# ATMega328-AD_DA_IO-V51-Eagle-Full.net
KiCad netlist of a schematic drawn in EAGLE
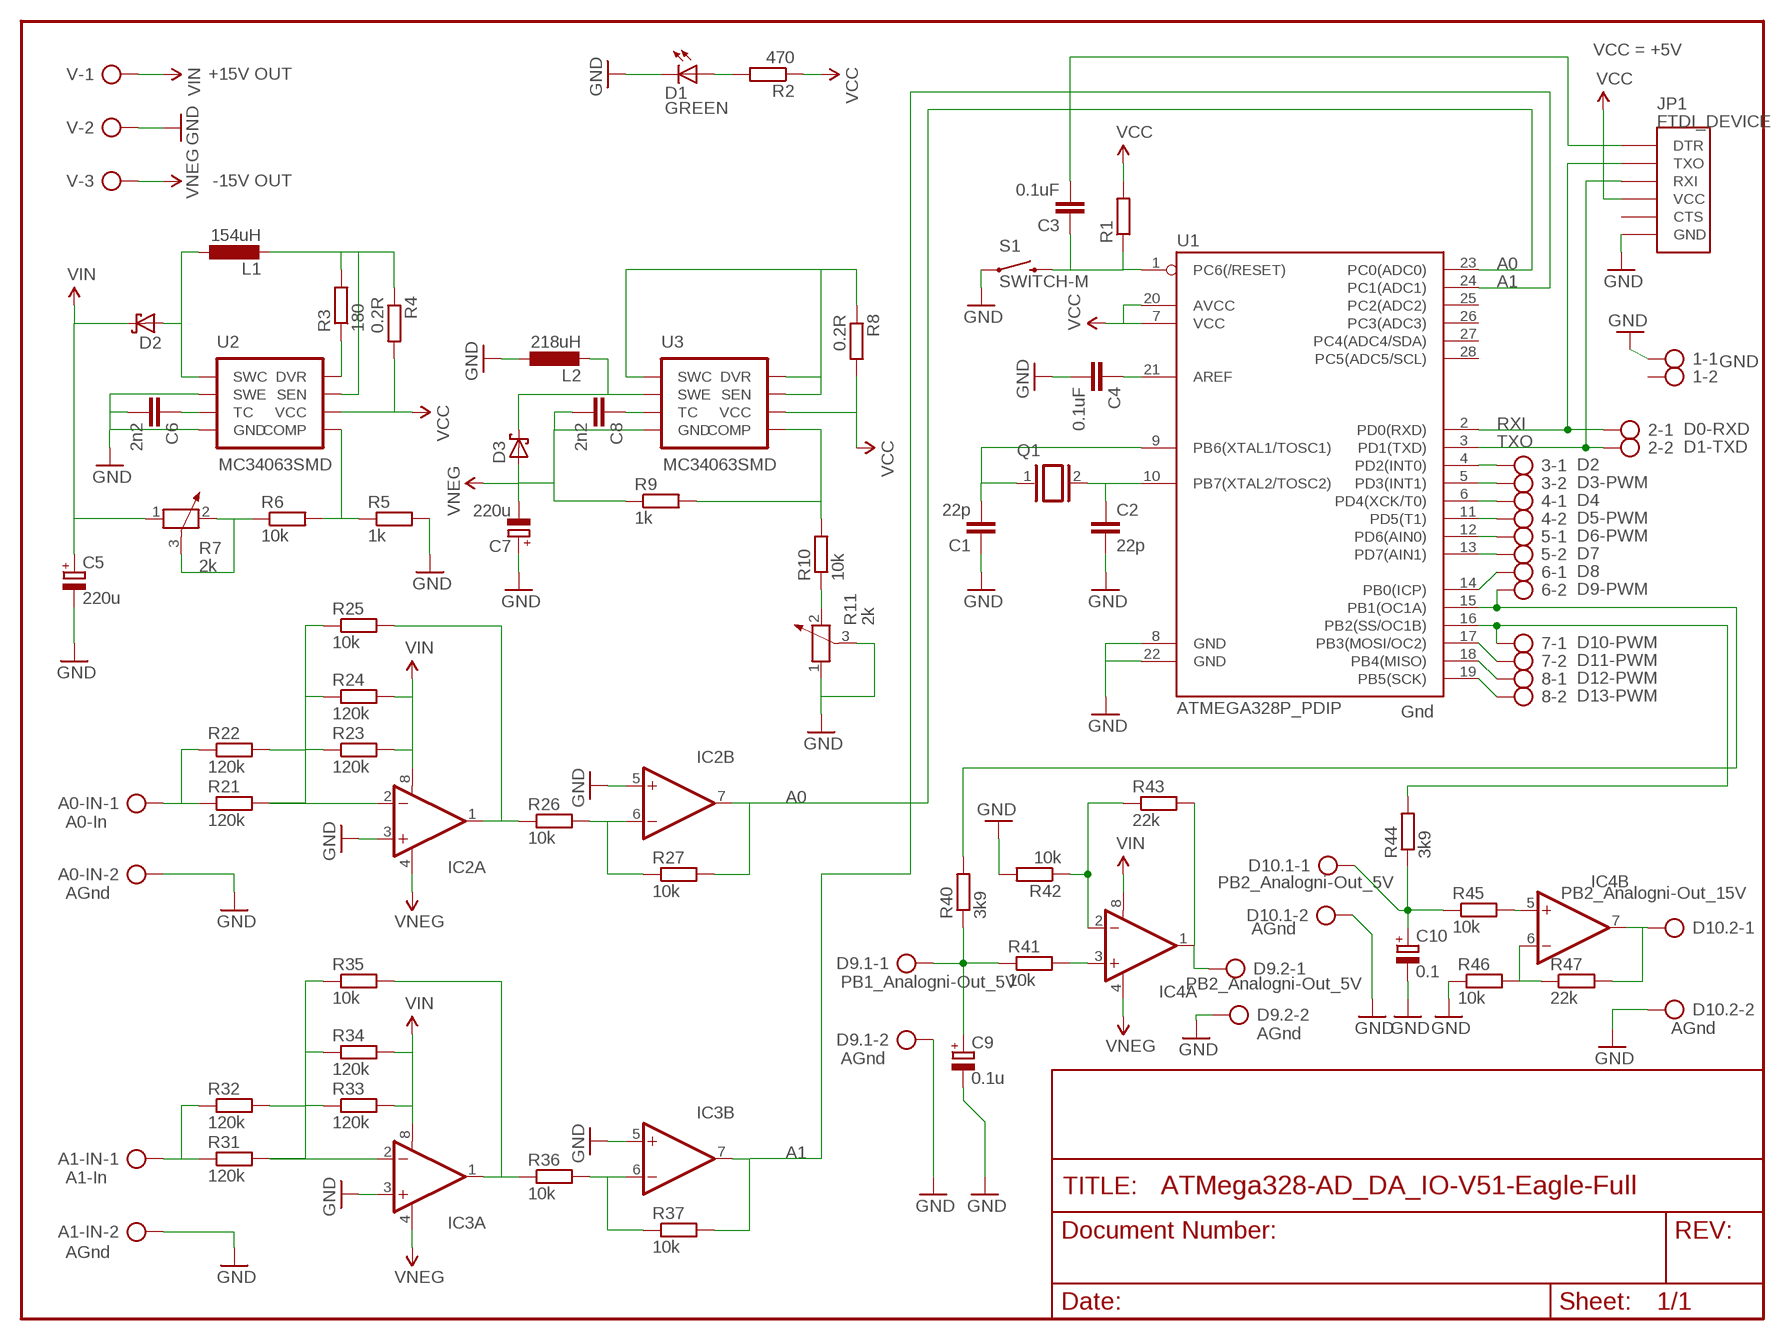
[diagram p0: schematic, sheet 1]

(export (version "E")
  (design (tool "Eeschema 10.0.6"))
  (components
    (comp (ref "1")
      (value "AK500/2")
      (footprint "eagle-import:AK500_2")
      (fields (field (name "OC_FARNELL") "unknown") (field (name "OC_NEWARK") "unknown"))
      (libsource (lib "eagle-import") (part "AK500/2"))
    )
    (comp (ref "2")
      (value "AK500/2")
      (footprint "eagle-import:AK500_2")
      (fields (field (name "OC_FARNELL") "unknown") (field (name "OC_NEWARK") "unknown"))
      (libsource (lib "eagle-import") (part "AK500/2"))
    )
    (comp (ref "3")
      (value "AK500/2")
      (footprint "eagle-import:AK500_2")
      (fields (field (name "OC_FARNELL") "unknown") (field (name "OC_NEWARK") "unknown"))
      (libsource (lib "eagle-import") (part "AK500/2"))
    )
    (comp (ref "4")
      (value "AK500/2")
      (footprint "eagle-import:AK500_2")
      (fields (field (name "OC_FARNELL") "unknown") (field (name "OC_NEWARK") "unknown"))
      (libsource (lib "eagle-import") (part "AK500/2"))
    )
    (comp (ref "5")
      (value "AK500/2")
      (footprint "eagle-import:AK500_2")
      (fields (field (name "OC_FARNELL") "unknown") (field (name "OC_NEWARK") "unknown"))
      (libsource (lib "eagle-import") (part "AK500/2"))
    )
    (comp (ref "6")
      (value "AK500/2")
      (footprint "eagle-import:AK500_2")
      (fields (field (name "OC_FARNELL") "unknown") (field (name "OC_NEWARK") "unknown"))
      (libsource (lib "eagle-import") (part "AK500/2"))
    )
    (comp (ref "7")
      (value "AK500/2")
      (footprint "eagle-import:AK500_2")
      (fields (field (name "OC_FARNELL") "unknown") (field (name "OC_NEWARK") "unknown"))
      (libsource (lib "eagle-import") (part "AK500/2"))
    )
    (comp (ref "8")
      (value "AK500/2")
      (footprint "eagle-import:AK500_2")
      (fields (field (name "OC_FARNELL") "unknown") (field (name "OC_NEWARK") "unknown"))
      (libsource (lib "eagle-import") (part "AK500/2"))
    )
    (comp (ref "A0-IN")
      (value "AK500/2")
      (footprint "eagle-import:AK500_2")
      (libsource (lib "eagle-import") (part "AK500/2"))
    )
    (comp (ref "A1-IN")
      (value "AK500/2")
      (footprint "eagle-import:AK500_2")
      (fields (field (name "OC_FARNELL") "unknown") (field (name "OC_NEWARK") "unknown"))
      (libsource (lib "eagle-import") (part "AK500/2"))
    )
    (comp (ref "C1")
      (value "22p")
      (footprint "eagle-import:C0805K")
      (libsource (lib "eagle-import") (part "C-EUC0805K"))
    )
    (comp (ref "C2")
      (value "22p")
      (footprint "eagle-import:C0805K")
      (libsource (lib "eagle-import") (part "C-EUC0805K"))
    )
    (comp (ref "C3")
      (value "0.1uF")
      (footprint "eagle-import:C0805K")
      (libsource (lib "eagle-import") (part "C-EUC0805K"))
    )
    (comp (ref "C4")
      (value "0.1uF")
      (footprint "eagle-import:C0805K")
      (libsource (lib "eagle-import") (part "C-EUC0805K"))
    )
    (comp (ref "C5")
      (value "220u")
      (footprint "eagle-import:E3,5-10")
      (libsource (lib "eagle-import") (part "CPOL-EUE3.5-10"))
    )
    (comp (ref "C6")
      (value "2n2")
      (footprint "eagle-import:C0805K")
      (libsource (lib "eagle-import") (part "C-EUC0805K"))
    )
    (comp (ref "C7")
      (value "220u")
      (footprint "eagle-import:E3,5-10")
      (libsource (lib "eagle-import") (part "CPOL-EUE3.5-10"))
    )
    (comp (ref "C8")
      (value "2n2")
      (footprint "eagle-import:C0805K")
      (libsource (lib "eagle-import") (part "C-EUC0805K"))
    )
    (comp (ref "C9")
      (value "0.1u")
      (footprint "eagle-import:E2,5-5")
      (libsource (lib "eagle-import") (part "CPOL-EUE2.5-5"))
    )
    (comp (ref "C10")
      (value "0.1")
      (footprint "eagle-import:E2,5-5")
      (libsource (lib "eagle-import") (part "CPOL-EUE2.5-5"))
    )
    (comp (ref "D1")
      (value "GREEN")
      (footprint "eagle-import:LED-1206")
      (libsource (lib "eagle-import") (part "LED-GREENLARGE"))
    )
    (comp (ref "D2")
      (value "SCHOTTKY-DIODESMD")
      (footprint "eagle-import:SMB")
      (libsource (lib "eagle-import") (part "SCHOTTKY-DIODESMD"))
    )
    (comp (ref "D3")
      (value "SCHOTTKY-DIODESMD")
      (footprint "eagle-import:SMB")
      (libsource (lib "eagle-import") (part "SCHOTTKY-DIODESMD"))
    )
    (comp (ref "D9.1")
      (value "AK500/2")
      (footprint "eagle-import:AK500_2")
      (fields (field (name "OC_FARNELL") "unknown") (field (name "OC_NEWARK") "unknown"))
      (libsource (lib "eagle-import") (part "AK500/2"))
    )
    (comp (ref "D9.2")
      (value "AK500/2")
      (footprint "eagle-import:AK500_2")
      (fields (field (name "OC_FARNELL") "unknown") (field (name "OC_NEWARK") "unknown"))
      (libsource (lib "eagle-import") (part "AK500/2"))
    )
    (comp (ref "D10.1")
      (value "AK500/2")
      (footprint "eagle-import:AK500_2")
      (fields (field (name "OC_FARNELL") "unknown") (field (name "OC_NEWARK") "unknown"))
      (libsource (lib "eagle-import") (part "AK500/2"))
    )
    (comp (ref "D10.2")
      (value "AK500/2")
      (footprint "eagle-import:AK500_2")
      (fields (field (name "OC_FARNELL") "unknown") (field (name "OC_NEWARK") "unknown"))
      (libsource (lib "eagle-import") (part "AK500/2"))
    )
    (comp (ref "IC2")
      (value "OPAMP-DUALU")
      (footprint "eagle-import:SO08")
      (libsource (lib "eagle-import") (part "OPAMP-DUALU"))
    )
    (comp (ref "IC3")
      (value "OPAMP-DUALU")
      (footprint "eagle-import:SO08")
      (libsource (lib "eagle-import") (part "OPAMP-DUALU"))
    )
    (comp (ref "IC4")
      (value "OPAMP-DUALU")
      (footprint "eagle-import:SO08")
      (libsource (lib "eagle-import") (part "OPAMP-DUALU"))
    )
    (comp (ref "JP1")
      (value "FTDI_DEVICE")
      (footprint "eagle-import:FTDI_DEVICE_SIDE")
      (libsource (lib "eagle-import") (part "FTDI_DEVICE"))
    )
    (comp (ref "L1")
      (value "154uH")
      (footprint "eagle-import:0207_2V")
      (libsource (lib "eagle-import") (part "L-EU0207/2V"))
    )
    (comp (ref "L2")
      (value "218uH")
      (footprint "eagle-import:0207_2V")
      (libsource (lib "eagle-import") (part "L-EU0207/2V"))
    )
    (comp (ref "Q1")
      (value "XTAL/S")
      (footprint "eagle-import:QS")
      (libsource (lib "eagle-import") (part "XTAL/S"))
    )
    (comp (ref "R1")
      (value "R-EU_M0805")
      (footprint "eagle-import:M0805")
      (libsource (lib "eagle-import") (part "R-EU_M0805"))
    )
    (comp (ref "R2")
      (value "470")
      (footprint "eagle-import:M0805")
      (libsource (lib "eagle-import") (part "R-EU_M0805"))
    )
    (comp (ref "R3")
      (value "180")
      (footprint "eagle-import:M0805")
      (libsource (lib "eagle-import") (part "R-EU_M0805"))
    )
    (comp (ref "R4")
      (value "0.2R")
      (footprint "eagle-import:0411_12")
      (libsource (lib "eagle-import") (part "R-EU_0411/12"))
    )
    (comp (ref "R5")
      (value "1k")
      (footprint "eagle-import:M0805")
      (libsource (lib "eagle-import") (part "R-EU_M0805"))
    )
    (comp (ref "R6")
      (value "10k")
      (footprint "eagle-import:M0805")
      (libsource (lib "eagle-import") (part "R-EU_M0805"))
    )
    (comp (ref "R7")
      (value "2k")
      (footprint "eagle-import:PT-10S")
      (libsource (lib "eagle-import") (part "POTENTIOMETER_PT-10S"))
    )
    (comp (ref "R8")
      (value "0.2R")
      (footprint "eagle-import:0411_12")
      (libsource (lib "eagle-import") (part "R-EU_0411/12"))
    )
    (comp (ref "R9")
      (value "1k")
      (footprint "eagle-import:M0805")
      (libsource (lib "eagle-import") (part "R-EU_M0805"))
    )
    (comp (ref "R10")
      (value "10k")
      (footprint "eagle-import:M0805")
      (libsource (lib "eagle-import") (part "R-EU_M0805"))
    )
    (comp (ref "R11")
      (value "2k")
      (footprint "eagle-import:PT-10S")
      (libsource (lib "eagle-import") (part "POTENTIOMETER_PT-10S"))
    )
    (comp (ref "R21")
      (value "120k")
      (footprint "eagle-import:M0805")
      (libsource (lib "eagle-import") (part "R-EU_M0805"))
    )
    (comp (ref "R22")
      (value "120k")
      (footprint "eagle-import:M0805")
      (libsource (lib "eagle-import") (part "R-EU_M0805"))
    )
    (comp (ref "R23")
      (value "120k")
      (footprint "eagle-import:M0805")
      (libsource (lib "eagle-import") (part "R-EU_M0805"))
    )
    (comp (ref "R24")
      (value "120k")
      (footprint "eagle-import:M0805")
      (libsource (lib "eagle-import") (part "R-EU_M0805"))
    )
    (comp (ref "R25")
      (value "10k")
      (footprint "eagle-import:M0805")
      (libsource (lib "eagle-import") (part "R-EU_M0805"))
    )
    (comp (ref "R26")
      (value "10k")
      (footprint "eagle-import:M0805")
      (libsource (lib "eagle-import") (part "R-EU_M0805"))
    )
    (comp (ref "R27")
      (value "10k")
      (footprint "eagle-import:M0805")
      (libsource (lib "eagle-import") (part "R-EU_M0805"))
    )
    (comp (ref "R31")
      (value "120k")
      (footprint "eagle-import:M0805")
      (libsource (lib "eagle-import") (part "R-EU_M0805"))
    )
    (comp (ref "R32")
      (value "120k")
      (footprint "eagle-import:M0805")
      (libsource (lib "eagle-import") (part "R-EU_M0805"))
    )
    (comp (ref "R33")
      (value "120k")
      (footprint "eagle-import:M0805")
      (libsource (lib "eagle-import") (part "R-EU_M0805"))
    )
    (comp (ref "R34")
      (value "120k")
      (footprint "eagle-import:M0805")
      (libsource (lib "eagle-import") (part "R-EU_M0805"))
    )
    (comp (ref "R35")
      (value "10k")
      (footprint "eagle-import:M0805")
      (libsource (lib "eagle-import") (part "R-EU_M0805"))
    )
    (comp (ref "R36")
      (value "10k")
      (footprint "eagle-import:M0805")
      (libsource (lib "eagle-import") (part "R-EU_M0805"))
    )
    (comp (ref "R37")
      (value "10k")
      (footprint "eagle-import:M0805")
      (libsource (lib "eagle-import") (part "R-EU_M0805"))
    )
    (comp (ref "R40")
      (value "3k9")
      (footprint "eagle-import:M0805")
      (libsource (lib "eagle-import") (part "R-EU_M0805"))
    )
    (comp (ref "R41")
      (value "10k")
      (footprint "eagle-import:M0805")
      (libsource (lib "eagle-import") (part "R-EU_M0805"))
    )
    (comp (ref "R42")
      (value "10k")
      (footprint "eagle-import:M0805")
      (libsource (lib "eagle-import") (part "R-EU_M0805"))
    )
    (comp (ref "R43")
      (value "22k")
      (footprint "eagle-import:M0805")
      (libsource (lib "eagle-import") (part "R-EU_M0805"))
    )
    (comp (ref "R44")
      (value "3k9")
      (footprint "eagle-import:M0805")
      (libsource (lib "eagle-import") (part "R-EU_M0805"))
    )
    (comp (ref "R45")
      (value "10k")
      (footprint "eagle-import:M0805")
      (libsource (lib "eagle-import") (part "R-EU_M0805"))
    )
    (comp (ref "R46")
      (value "10k")
      (footprint "eagle-import:M0805")
      (libsource (lib "eagle-import") (part "R-EU_M0805"))
    )
    (comp (ref "R47")
      (value "22k")
      (footprint "eagle-import:M0805")
      (libsource (lib "eagle-import") (part "R-EU_M0805"))
    )
    (comp (ref "S1")
      (value "SWITCH-M")
      (footprint "eagle-import:TACTILE-PTH")
      (libsource (lib "eagle-import") (part "SWITCH-MOMENTARY-2PTH"))
    )
    (comp (ref "U1")
      (value "ATMEGA328P_PDIP")
      (footprint "eagle-import:DIL28-3")
      (libsource (lib "eagle-import") (part "ATMEGA328P_PDIP"))
    )
    (comp (ref "U2")
      (value "MC34063SMD")
      (footprint "eagle-import:SO08")
      (libsource (lib "eagle-import") (part "MC34063SMD"))
    )
    (comp (ref "U3")
      (value "MC34063SMD")
      (footprint "eagle-import:SO08")
      (libsource (lib "eagle-import") (part "MC34063SMD"))
    )
    (comp (ref "V")
      (value "AK500/3")
      (footprint "eagle-import:AK500_3")
      (libsource (lib "eagle-import") (part "AK500/3"))
    )
  )
  (nets
    (net (code "1") (name "GND") (class "Default")
      (node (ref "1") (pin "1") (pinfunction "KL_1") (pintype "passive"))
      (node (ref "A0-IN") (pin "2") (pinfunction "KL_2") (pintype "passive"))
      (node (ref "A1-IN") (pin "2") (pinfunction "KL_2") (pintype "passive"))
      (node (ref "C1") (pin "1") (pinfunction "1_1") (pintype "passive"))
      (node (ref "C10") (pin "-") (pinfunction "-_-") (pintype "passive"))
      (node (ref "C2") (pin "2") (pinfunction "2_2") (pintype "passive"))
      (node (ref "C4") (pin "2") (pinfunction "2_2") (pintype "passive"))
      (node (ref "C5") (pin "-") (pinfunction "-_-") (pintype "passive"))
      (node (ref "C6") (pin "2") (pinfunction "2_2") (pintype "passive"))
      (node (ref "C7") (pin "+") (pinfunction "+_+") (pintype "passive"))
      (node (ref "C9") (pin "-") (pinfunction "-_-") (pintype "passive"))
      (node (ref "D1") (pin "C") (pinfunction "C_C") (pintype "passive"))
      (node (ref "D10.1") (pin "2") (pinfunction "KL_2") (pintype "passive"))
      (node (ref "D10.2") (pin "2") (pinfunction "KL_2") (pintype "passive"))
      (node (ref "D9.1") (pin "2") (pinfunction "KL_2") (pintype "passive"))
      (node (ref "D9.2") (pin "2") (pinfunction "KL_2") (pintype "passive"))
      (node (ref "IC2") (pin "3") (pinfunction "+IN_3") (pintype "input"))
      (node (ref "IC2") (pin "5") (pinfunction "+IN_5") (pintype "input"))
      (node (ref "IC3") (pin "3") (pinfunction "+IN_3") (pintype "input"))
      (node (ref "IC3") (pin "5") (pinfunction "+IN_5") (pintype "input"))
      (node (ref "JP1") (pin "P$6") (pinfunction "GND_P$6") (pintype "bidirectional"))
      (node (ref "L2") (pin "1") (pinfunction "1_1") (pintype "passive"))
      (node (ref "R11") (pin "1") (pinfunction "1_1") (pintype "passive"))
      (node (ref "R11") (pin "3") (pinfunction "3_3") (pintype "passive"))
      (node (ref "R42") (pin "2") (pinfunction "2_2") (pintype "passive"))
      (node (ref "R46") (pin "1") (pinfunction "1_1") (pintype "passive"))
      (node (ref "R5") (pin "2") (pinfunction "2_2") (pintype "passive"))
      (node (ref "S1") (pin "1") (pinfunction "1_1") (pintype "passive"))
      (node (ref "U1") (pin "22") (pinfunction "GND_22") (pintype "bidirectional"))
      (node (ref "U1") (pin "8") (pinfunction "GND_8") (pintype "bidirectional"))
      (node (ref "U2") (pin "2") (pinfunction "SWE_2") (pintype "bidirectional"))
      (node (ref "U2") (pin "4") (pinfunction "GND_4") (pintype "bidirectional"))
      (node (ref "V") (pin "2") (pinfunction "KL_2") (pintype "passive"))
    )
    (net (code "2") (name "Net-(2A-KL)") (class "Default")
      (node (ref "2") (pin "1") (pinfunction "KL_1") (pintype "passive"))
      (node (ref "JP1") (pin "P$2") (pinfunction "TXO_P$2") (pintype "bidirectional"))
      (node (ref "U1") (pin "2") (pinfunction "PD0(RXD)_2") (pintype "bidirectional"))
    )
    (net (code "3") (name "Net-(2B-KL)") (class "Default")
      (node (ref "2") (pin "2") (pinfunction "KL_2") (pintype "passive"))
      (node (ref "JP1") (pin "P$3") (pinfunction "RXI_P$3") (pintype "bidirectional"))
      (node (ref "U1") (pin "3") (pinfunction "PD1(TXD)_3") (pintype "bidirectional"))
    )
    (net (code "4") (name "Net-(3A-KL)") (class "Default")
      (node (ref "3") (pin "1") (pinfunction "KL_1") (pintype "passive"))
      (node (ref "U1") (pin "4") (pinfunction "PD2(INT0)_4") (pintype "bidirectional"))
    )
    (net (code "5") (name "Net-(3B-KL)") (class "Default")
      (node (ref "3") (pin "2") (pinfunction "KL_2") (pintype "passive"))
      (node (ref "U1") (pin "5") (pinfunction "PD3(INT1)_5") (pintype "bidirectional"))
    )
    (net (code "6") (name "Net-(4A-KL)") (class "Default")
      (node (ref "4") (pin "1") (pinfunction "KL_1") (pintype "passive"))
      (node (ref "U1") (pin "6") (pinfunction "PD4(XCK/T0)_6") (pintype "bidirectional"))
    )
    (net (code "7") (name "Net-(4B-KL)") (class "Default")
      (node (ref "4") (pin "2") (pinfunction "KL_2") (pintype "passive"))
      (node (ref "U1") (pin "11") (pinfunction "PD5(T1)_11") (pintype "bidirectional"))
    )
    (net (code "8") (name "Net-(5A-KL)") (class "Default")
      (node (ref "5") (pin "1") (pinfunction "KL_1") (pintype "passive"))
      (node (ref "U1") (pin "12") (pinfunction "PD6(AIN0)_12") (pintype "bidirectional"))
    )
    (net (code "9") (name "Net-(5B-KL)") (class "Default")
      (node (ref "5") (pin "2") (pinfunction "KL_2") (pintype "passive"))
      (node (ref "U1") (pin "13") (pinfunction "PD7(AIN1)_13") (pintype "bidirectional"))
    )
    (net (code "10") (name "Net-(6A-KL)") (class "Default")
      (node (ref "6") (pin "1") (pinfunction "KL_1") (pintype "passive"))
      (node (ref "U1") (pin "14") (pinfunction "PB0(ICP)_14") (pintype "bidirectional"))
    )
    (net (code "11") (name "Net-(6B-KL)") (class "Default")
      (node (ref "6") (pin "2") (pinfunction "KL_2") (pintype "passive"))
      (node (ref "R40") (pin "2") (pinfunction "2_2") (pintype "passive"))
      (node (ref "U1") (pin "15") (pinfunction "PB1(OC1A)_15") (pintype "bidirectional"))
    )
    (net (code "12") (name "Net-(7A-KL)") (class "Default")
      (node (ref "7") (pin "1") (pinfunction "KL_1") (pintype "passive"))
      (node (ref "R44") (pin "2") (pinfunction "2_2") (pintype "passive"))
      (node (ref "U1") (pin "16") (pinfunction "PB2(SS/OC1B)_16") (pintype "bidirectional"))
    )
    (net (code "13") (name "Net-(7B-KL)") (class "Default")
      (node (ref "7") (pin "2") (pinfunction "KL_2") (pintype "passive"))
      (node (ref "U1") (pin "17") (pinfunction "PB3(MOSI/OC2)_17") (pintype "bidirectional"))
    )
    (net (code "14") (name "Net-(8A-KL)") (class "Default")
      (node (ref "8") (pin "1") (pinfunction "KL_1") (pintype "passive"))
      (node (ref "U1") (pin "18") (pinfunction "PB4(MISO)_18") (pintype "bidirectional"))
    )
    (net (code "15") (name "Net-(8B-KL)") (class "Default")
      (node (ref "8") (pin "2") (pinfunction "KL_2") (pintype "passive"))
      (node (ref "U1") (pin "19") (pinfunction "PB5(SCK)_19") (pintype "bidirectional"))
    )
    (net (code "16") (name "Net-(A0-INA-KL)") (class "Default")
      (node (ref "A0-IN") (pin "1") (pinfunction "KL_1") (pintype "passive"))
      (node (ref "R21") (pin "1") (pinfunction "1_1") (pintype "passive"))
      (node (ref "R22") (pin "1") (pinfunction "1_1") (pintype "passive"))
    )
    (net (code "17") (name "Net-(A1-INA-KL)") (class "Default")
      (node (ref "A1-IN") (pin "1") (pinfunction "KL_1") (pintype "passive"))
      (node (ref "R31") (pin "1") (pinfunction "1_1") (pintype "passive"))
      (node (ref "R32") (pin "1") (pinfunction "1_1") (pintype "passive"))
    )
    (net (code "18") (name "Net-(D1-PadA)") (class "Default")
      (node (ref "D1") (pin "A") (pinfunction "A_A") (pintype "passive"))
      (node (ref "R2") (pin "2") (pinfunction "2_2") (pintype "passive"))
    )
    (net (code "19") (name "Net-(D9.1A-KL)") (class "Default")
      (node (ref "C9") (pin "+") (pinfunction "+_+") (pintype "passive"))
      (node (ref "D9.1") (pin "1") (pinfunction "KL_1") (pintype "passive"))
      (node (ref "R40") (pin "1") (pinfunction "1_1") (pintype "passive"))
      (node (ref "R41") (pin "1") (pinfunction "1_1") (pintype "passive"))
    )
    (net (code "20") (name "Net-(D9.2A-KL)") (class "Default")
      (node (ref "D9.2") (pin "1") (pinfunction "KL_1") (pintype "passive"))
      (node (ref "IC4") (pin "1") (pinfunction "OUT_1") (pintype "output"))
      (node (ref "R43") (pin "2") (pinfunction "2_2") (pintype "passive"))
    )
    (net (code "21") (name "Net-(D10.1A-KL)") (class "Default")
      (node (ref "C10") (pin "+") (pinfunction "+_+") (pintype "passive"))
      (node (ref "D10.1") (pin "1") (pinfunction "KL_1") (pintype "passive"))
      (node (ref "R44") (pin "1") (pinfunction "1_1") (pintype "passive"))
      (node (ref "R45") (pin "1") (pinfunction "1_1") (pintype "passive"))
    )
    (net (code "22") (name "Net-(D10.2A-KL)") (class "Default")
      (node (ref "D10.2") (pin "1") (pinfunction "KL_1") (pintype "passive"))
      (node (ref "IC4") (pin "7") (pinfunction "OUT_7") (pintype "output"))
      (node (ref "R47") (pin "2") (pinfunction "2_2") (pintype "passive"))
    )
    (net (code "23") (name "Net-(IC2A--IN)") (class "Default")
      (node (ref "IC2") (pin "2") (pinfunction "-IN_2") (pintype "input"))
      (node (ref "R21") (pin "2") (pinfunction "2_2") (pintype "passive"))
      (node (ref "R22") (pin "2") (pinfunction "2_2") (pintype "passive"))
      (node (ref "R23") (pin "1") (pinfunction "1_1") (pintype "passive"))
      (node (ref "R24") (pin "1") (pinfunction "1_1") (pintype "passive"))
      (node (ref "R25") (pin "1") (pinfunction "1_1") (pintype "passive"))
    )
    (net (code "24") (name "Net-(IC2A-OUT)") (class "Default")
      (node (ref "IC2") (pin "1") (pinfunction "OUT_1") (pintype "output"))
      (node (ref "R25") (pin "2") (pinfunction "2_2") (pintype "passive"))
      (node (ref "R26") (pin "1") (pinfunction "1_1") (pintype "passive"))
    )
    (net (code "25") (name "Net-(IC2B--IN)") (class "Default")
      (node (ref "IC2") (pin "6") (pinfunction "-IN_6") (pintype "input"))
      (node (ref "R26") (pin "2") (pinfunction "2_2") (pintype "passive"))
      (node (ref "R27") (pin "1") (pinfunction "1_1") (pintype "passive"))
    )
    (net (code "26") (name "Net-(IC2B-OUT)") (class "Default")
      (node (ref "IC2") (pin "7") (pinfunction "OUT_7") (pintype "output"))
      (node (ref "R27") (pin "2") (pinfunction "2_2") (pintype "passive"))
      (node (ref "U1") (pin "23") (pinfunction "PC0(ADC0)_23") (pintype "bidirectional"))
    )
    (net (code "27") (name "Net-(IC3A--IN)") (class "Default")
      (node (ref "IC3") (pin "2") (pinfunction "-IN_2") (pintype "input"))
      (node (ref "R31") (pin "2") (pinfunction "2_2") (pintype "passive"))
      (node (ref "R32") (pin "2") (pinfunction "2_2") (pintype "passive"))
      (node (ref "R33") (pin "1") (pinfunction "1_1") (pintype "passive"))
      (node (ref "R34") (pin "1") (pinfunction "1_1") (pintype "passive"))
      (node (ref "R35") (pin "1") (pinfunction "1_1") (pintype "passive"))
    )
    (net (code "28") (name "Net-(IC3A-OUT)") (class "Default")
      (node (ref "IC3") (pin "1") (pinfunction "OUT_1") (pintype "output"))
      (node (ref "R35") (pin "2") (pinfunction "2_2") (pintype "passive"))
      (node (ref "R36") (pin "1") (pinfunction "1_1") (pintype "passive"))
    )
    (net (code "29") (name "Net-(IC3B--IN)") (class "Default")
      (node (ref "IC3") (pin "6") (pinfunction "-IN_6") (pintype "input"))
      (node (ref "R36") (pin "2") (pinfunction "2_2") (pintype "passive"))
      (node (ref "R37") (pin "1") (pinfunction "1_1") (pintype "passive"))
    )
    (net (code "30") (name "Net-(IC3B-OUT)") (class "Default")
      (node (ref "IC3") (pin "7") (pinfunction "OUT_7") (pintype "output"))
      (node (ref "R37") (pin "2") (pinfunction "2_2") (pintype "passive"))
      (node (ref "U1") (pin "24") (pinfunction "PC1(ADC1)_24") (pintype "bidirectional"))
    )
    (net (code "31") (name "Net-(IC4A-+IN)") (class "Default")
      (node (ref "IC4") (pin "3") (pinfunction "+IN_3") (pintype "input"))
      (node (ref "R41") (pin "2") (pinfunction "2_2") (pintype "passive"))
    )
    (net (code "32") (name "Net-(IC4A--IN)") (class "Default")
      (node (ref "IC4") (pin "2") (pinfunction "-IN_2") (pintype "input"))
      (node (ref "R42") (pin "1") (pinfunction "1_1") (pintype "passive"))
      (node (ref "R43") (pin "1") (pinfunction "1_1") (pintype "passive"))
    )
    (net (code "33") (name "Net-(IC4B-+IN)") (class "Default")
      (node (ref "IC4") (pin "5") (pinfunction "+IN_5") (pintype "input"))
      (node (ref "R45") (pin "2") (pinfunction "2_2") (pintype "passive"))
    )
    (net (code "34") (name "Net-(IC4B--IN)") (class "Default")
      (node (ref "IC4") (pin "6") (pinfunction "-IN_6") (pintype "input"))
      (node (ref "R46") (pin "2") (pinfunction "2_2") (pintype "passive"))
      (node (ref "R47") (pin "1") (pinfunction "1_1") (pintype "passive"))
    )
    (net (code "35") (name "Net-(JP1-DTR)") (class "Default")
      (node (ref "C3") (pin "2") (pinfunction "2_2") (pintype "passive"))
      (node (ref "JP1") (pin "P$1") (pinfunction "DTR_P$1") (pintype "bidirectional"))
    )
    (net (code "36") (name "Net-(R6-Pad1)") (class "Default")
      (node (ref "R6") (pin "1") (pinfunction "1_1") (pintype "passive"))
      (node (ref "R7") (pin "2") (pinfunction "2_2") (pintype "passive"))
      (node (ref "R7") (pin "3") (pinfunction "3_3") (pintype "passive"))
    )
    (net (code "37") (name "Net-(R10-Pad1)") (class "Default")
      (node (ref "R10") (pin "1") (pinfunction "1_1") (pintype "passive"))
      (node (ref "R11") (pin "2") (pinfunction "2_2") (pintype "passive"))
    )
    (net (code "38") (name "Net-(S1-2)") (class "Default")
      (node (ref "C3") (pin "1") (pinfunction "1_1") (pintype "passive"))
      (node (ref "R1") (pin "1") (pinfunction "1_1") (pintype "passive"))
      (node (ref "S1") (pin "3") (pinfunction "2_3") (pintype "passive"))
      (node (ref "U1") (pin "1") (pinfunction "PC6(/RESET)_1") (pintype "bidirectional"))
    )
    (net (code "39") (name "Net-(U1-AREF)") (class "Default")
      (node (ref "C4") (pin "1") (pinfunction "1_1") (pintype "passive"))
      (node (ref "U1") (pin "21") (pinfunction "AREF_21") (pintype "bidirectional"))
    )
    (net (code "40") (name "Net-(U1-PB6(XTAL1{slash}TOSC1))") (class "Default")
      (node (ref "C1") (pin "2") (pinfunction "2_2") (pintype "passive"))
      (node (ref "Q1") (pin "1") (pinfunction "1_1") (pintype "passive"))
      (node (ref "U1") (pin "9") (pinfunction "PB6(XTAL1/TOSC1)_9") (pintype "bidirectional"))
    )
    (net (code "41") (name "Net-(U1-PB7(XTAL2{slash}TOSC2))") (class "Default")
      (node (ref "C2") (pin "1") (pinfunction "1_1") (pintype "passive"))
      (node (ref "Q1") (pin "2") (pinfunction "2_2") (pintype "passive"))
      (node (ref "U1") (pin "10") (pinfunction "PB7(XTAL2/TOSC2)_10") (pintype "bidirectional"))
    )
    (net (code "42") (name "Net-(U2-COMP)") (class "Default")
      (node (ref "R5") (pin "1") (pinfunction "1_1") (pintype "passive"))
      (node (ref "R6") (pin "2") (pinfunction "2_2") (pintype "passive"))
      (node (ref "U2") (pin "5") (pinfunction "COMP_5") (pintype "bidirectional"))
    )
    (net (code "43") (name "Net-(U2-DVR)") (class "Default")
      (node (ref "R3") (pin "1") (pinfunction "1_1") (pintype "passive"))
      (node (ref "U2") (pin "8") (pinfunction "DVR_8") (pintype "bidirectional"))
    )
    (net (code "44") (name "Net-(U2-SEN)") (class "Default")
      (node (ref "L1") (pin "2") (pinfunction "2_2") (pintype "passive"))
      (node (ref "R3") (pin "2") (pinfunction "2_2") (pintype "passive"))
      (node (ref "R4") (pin "1") (pinfunction "1_1") (pintype "passive"))
      (node (ref "U2") (pin "7") (pinfunction "SEN_7") (pintype "bidirectional"))
    )
    (net (code "45") (name "Net-(U2-SWC)") (class "Default")
      (node (ref "D2") (pin "A") (pinfunction "A_A") (pintype "passive"))
      (node (ref "L1") (pin "1") (pinfunction "1_1") (pintype "passive"))
      (node (ref "U2") (pin "1") (pinfunction "SWC_1") (pintype "bidirectional"))
    )
    (net (code "46") (name "Net-(U2-TC)") (class "Default")
      (node (ref "C6") (pin "1") (pinfunction "1_1") (pintype "passive"))
      (node (ref "U2") (pin "3") (pinfunction "TC_3") (pintype "bidirectional"))
    )
    (net (code "47") (name "Net-(U3-COMP)") (class "Default")
      (node (ref "R10") (pin "2") (pinfunction "2_2") (pintype "passive"))
      (node (ref "R9") (pin "2") (pinfunction "2_2") (pintype "passive"))
      (node (ref "U3") (pin "5") (pinfunction "COMP_5") (pintype "bidirectional"))
    )
    (net (code "48") (name "Net-(U3-DVR)") (class "Default")
      (node (ref "R8") (pin "1") (pinfunction "1_1") (pintype "passive"))
      (node (ref "U3") (pin "1") (pinfunction "SWC_1") (pintype "bidirectional"))
      (node (ref "U3") (pin "7") (pinfunction "SEN_7") (pintype "bidirectional"))
      (node (ref "U3") (pin "8") (pinfunction "DVR_8") (pintype "bidirectional"))
    )
    (net (code "49") (name "Net-(U3-SWE)") (class "Default")
      (node (ref "D3") (pin "C") (pinfunction "C_C") (pintype "passive"))
      (node (ref "L2") (pin "2") (pinfunction "2_2") (pintype "passive"))
      (node (ref "U3") (pin "2") (pinfunction "SWE_2") (pintype "bidirectional"))
    )
    (net (code "50") (name "Net-(U3-TC)") (class "Default")
      (node (ref "C8") (pin "1") (pinfunction "1_1") (pintype "passive"))
      (node (ref "U3") (pin "3") (pinfunction "TC_3") (pintype "bidirectional"))
    )
    (net (code "51") (name "VCC") (class "Default")
      (node (ref "JP1") (pin "P$4") (pinfunction "VCC_P$4") (pintype "bidirectional"))
      (node (ref "R1") (pin "2") (pinfunction "2_2") (pintype "passive"))
      (node (ref "R2") (pin "1") (pinfunction "1_1") (pintype "passive"))
      (node (ref "R4") (pin "2") (pinfunction "2_2") (pintype "passive"))
      (node (ref "R8") (pin "2") (pinfunction "2_2") (pintype "passive"))
      (node (ref "U1") (pin "20") (pinfunction "AVCC_20") (pintype "bidirectional"))
      (node (ref "U1") (pin "7") (pinfunction "VCC_7") (pintype "bidirectional"))
      (node (ref "U2") (pin "6") (pinfunction "VCC_6") (pintype "bidirectional"))
      (node (ref "U3") (pin "6") (pinfunction "VCC_6") (pintype "bidirectional"))
    )
    (net (code "52") (name "VIN") (class "Default")
      (node (ref "C5") (pin "+") (pinfunction "+_+") (pintype "passive"))
      (node (ref "D2") (pin "C") (pinfunction "C_C") (pintype "passive"))
      (node (ref "IC2") (pin "8") (pinfunction "V+_8") (pintype "power_in"))
      (node (ref "IC3") (pin "8") (pinfunction "V+_8") (pintype "power_in"))
      (node (ref "IC4") (pin "8") (pinfunction "V+_8") (pintype "power_in"))
      (node (ref "R23") (pin "2") (pinfunction "2_2") (pintype "passive"))
      (node (ref "R24") (pin "2") (pinfunction "2_2") (pintype "passive"))
      (node (ref "R33") (pin "2") (pinfunction "2_2") (pintype "passive"))
      (node (ref "R34") (pin "2") (pinfunction "2_2") (pintype "passive"))
      (node (ref "R7") (pin "1") (pinfunction "1_1") (pintype "passive"))
      (node (ref "V") (pin "1") (pinfunction "KL_1") (pintype "passive"))
    )
    (net (code "53") (name "VNEG") (class "Default")
      (node (ref "C7") (pin "-") (pinfunction "-_-") (pintype "passive"))
      (node (ref "C8") (pin "2") (pinfunction "2_2") (pintype "passive"))
      (node (ref "D3") (pin "A") (pinfunction "A_A") (pintype "passive"))
      (node (ref "IC2") (pin "4") (pinfunction "V-_4") (pintype "power_in"))
      (node (ref "IC3") (pin "4") (pinfunction "V-_4") (pintype "power_in"))
      (node (ref "IC4") (pin "4") (pinfunction "V-_4") (pintype "power_in"))
      (node (ref "R9") (pin "1") (pinfunction "1_1") (pintype "passive"))
      (node (ref "U3") (pin "4") (pinfunction "GND_4") (pintype "bidirectional"))
      (node (ref "V") (pin "3") (pinfunction "KL_3") (pintype "passive"))
    )
    (net (code "54") (name "unconnected-(1B-KL-Pad2)") (class "Default")
      (node (ref "1") (pin "2") (pinfunction "KL_2") (pintype "passive"))
    )
    (net (code "55") (name "unconnected-(JP1-CTS-PadP$5)") (class "Default")
      (node (ref "JP1") (pin "P$5") (pinfunction "CTS_P$5") (pintype "bidirectional"))
    )
    (net (code "56") (name "unconnected-(U1-PC2(ADC2)-Pad25)") (class "Default")
      (node (ref "U1") (pin "25") (pinfunction "PC2(ADC2)_25") (pintype "bidirectional"))
    )
    (net (code "57") (name "unconnected-(U1-PC3(ADC3)-Pad26)") (class "Default")
      (node (ref "U1") (pin "26") (pinfunction "PC3(ADC3)_26") (pintype "bidirectional"))
    )
    (net (code "58") (name "unconnected-(U1-PC4(ADC4{slash}SDA)-Pad27)") (class "Default")
      (node (ref "U1") (pin "27") (pinfunction "PC4(ADC4/SDA)_27") (pintype "bidirectional"))
    )
    (net (code "59") (name "unconnected-(U1-PC5(ADC5{slash}SCL)-Pad28)") (class "Default")
      (node (ref "U1") (pin "28") (pinfunction "PC5(ADC5/SCL)_28") (pintype "bidirectional"))
    )
  )
)
